# dac_audio_out.net
KiCad netlist of a schematic drawn in Altium Designer
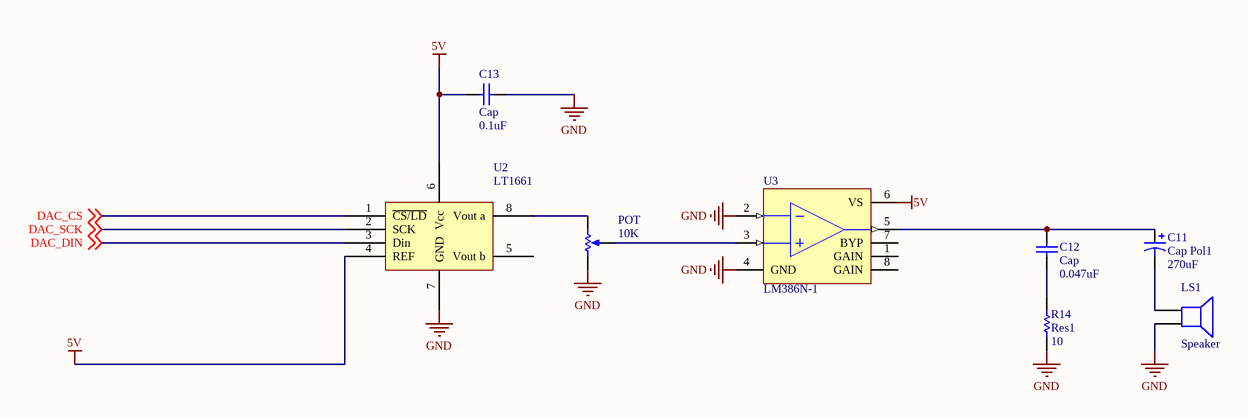
[diagram p0: dac_audio_out.SchDoc]

(export (version "E")
  (design (tool "Eeschema 10.0.6"))
  (components
    (comp (ref "C11")
      (value "Cap Pol1")
      (footprint "6-0805_M")
      (description "Polarized Capacitor (Radial)")
      (fields (field (name "ALTIUM_VALUE") "270uF") (field (name "PUBLISHER") "Altium Limited"))
      (libsource (lib "Miscellaneous Devices") (part "Cap Pol1"))
    )
    (comp (ref "C12")
      (value "Cap")
      (footprint "6-0805_M")
      (description "Capacitor")
      (fields (field (name "ALTIUM_VALUE") "0.047uF") (field (name "PUBLISHER") "Altium Limited"))
      (libsource (lib "Miscellaneous Devices") (part "Cap"))
    )
    (comp (ref "C13")
      (value "Cap")
      (footprint "6-0805_M")
      (description "Capacitor")
      (fields (field (name "ALTIUM_VALUE") "0.1uF") (field (name "PUBLISHER") "Altium Limited"))
      (libsource (lib "Miscellaneous Devices") (part "Cap"))
    )
    (comp (ref "LS1")
      (value "Speaker")
      (footprint "PIN2")
      (description "Loudspeaker")
      (fields (field (name "PUBLISHER") "Altium Limited"))
      (libsource (lib "Miscellaneous Devices") (part "Speaker"))
    )
    (comp (ref "POT")
      (value "10K")
      (footprint "VR5")
      (description "Potentiometer")
      (fields (field (name "Comment") "RPot_3") (field (name "PUBLISHER") "Altium Limited"))
      (libsource (lib "ECE LIB new") (part "RPot"))
    )
    (comp (ref "R14")
      (value "Res1")
      (footprint "6-0805_M")
      (description "Resistor")
      (fields (field (name "ALTIUM_VALUE") "10") (field (name "PUBLISHER") "Altium Limited"))
      (libsource (lib "Miscellaneous Devices") (part "Res1"))
    )
    (comp (ref "U2") (value "LT1661") (footprint "DIP-8") (libsource (lib "ECE LIB new") (part "LT1661")))
    (comp (ref "U3")
      (value "LM386N-1")
      (footprint "DIP-8")
      (description "Low-Voltage Audio Power Amplifier")
      (fields (field (name "PUBLISHER") "Altium Limited"))
      (libsource (lib "ECE LIB new") (part "LM386N-1"))
    )
  )
  (nets
    (net (code "1") (name "5V") (class "Default")
      (node (ref "C13") (pin "1") (pinfunction "1_1") (pintype "passive"))
      (node (ref "U2") (pin "4") (pinfunction "REF_4") (pintype "passive"))
      (node (ref "U2") (pin "6") (pinfunction "Vcc_6") (pintype "passive"))
      (node (ref "U3") (pin "6") (pinfunction "VS_6") (pintype "power_in"))
    )
    (net (code "2") (name "DAC_CS") (class "Default")
      (node (ref "U2") (pin "1") (pinfunction "~{CS/LD}_1") (pintype "passive"))
    )
    (net (code "3") (name "DAC_DIN") (class "Default")
      (node (ref "U2") (pin "3") (pinfunction "Din_3") (pintype "passive"))
    )
    (net (code "4") (name "DAC_SCK") (class "Default")
      (node (ref "U2") (pin "2") (pinfunction "SCK_2") (pintype "passive"))
    )
    (net (code "5") (name "GND") (class "Default")
      (node (ref "C13") (pin "2") (pinfunction "2_2") (pintype "passive"))
      (node (ref "LS1") (pin "2") (pinfunction "2_2") (pintype "passive"))
      (node (ref "POT") (pin "1") (pinfunction "TOP_1") (pintype "passive"))
      (node (ref "R14") (pin "1") (pinfunction "1_1") (pintype "passive"))
      (node (ref "U2") (pin "7") (pinfunction "GND_7") (pintype "passive"))
      (node (ref "U3") (pin "2") (pinfunction "IN-_2") (pintype "input"))
      (node (ref "U3") (pin "4") (pinfunction "GND_4") (pintype "power_in"))
    )
    (net (code "6") (name "Net-(C11-Pad2)") (class "Default")
      (node (ref "C11") (pin "2") (pinfunction "2_2") (pintype "passive"))
      (node (ref "LS1") (pin "1") (pinfunction "1_1") (pintype "passive"))
    )
    (net (code "7") (name "Net-(C12-Pad1)") (class "Default")
      (node (ref "C12") (pin "1") (pinfunction "1_1") (pintype "passive"))
      (node (ref "R14") (pin "2") (pinfunction "2_2") (pintype "passive"))
    )
    (net (code "8") (name "Net-(POT-BOT)") (class "Default")
      (node (ref "POT") (pin "3") (pinfunction "BOT_3") (pintype "passive"))
      (node (ref "U2") (pin "8") (pinfunction "Vout_a_8") (pintype "passive"))
    )
    (net (code "9") (name "Net-(POT-TAP)") (class "Default")
      (node (ref "POT") (pin "2") (pinfunction "TAP_2") (pintype "passive"))
      (node (ref "U3") (pin "3") (pinfunction "IN+_3") (pintype "input"))
    )
    (net (code "10") (name "Net-(U3-OUT)") (class "Default")
      (node (ref "C11") (pin "1") (pinfunction "1_1") (pintype "passive"))
      (node (ref "C12") (pin "2") (pinfunction "2_2") (pintype "passive"))
      (node (ref "U3") (pin "5") (pinfunction "OUT_5") (pintype "output"))
    )
    (net (code "11") (name "unconnected-(U2-Vout_b-Pad5)") (class "Default")
      (node (ref "U2") (pin "5") (pinfunction "Vout_b_5") (pintype "passive"))
    )
    (net (code "12") (name "unconnected-(U3-BYP-Pad7)") (class "Default")
      (node (ref "U3") (pin "7") (pinfunction "BYP_7") (pintype "passive"))
    )
    (net (code "13") (name "unconnected-(U3-GAIN-Pad1)") (class "Default")
      (node (ref "U3") (pin "1") (pinfunction "GAIN_1") (pintype "passive"))
    )
    (net (code "14") (name "unconnected-(U3-GAIN-Pad8)") (class "Default")
      (node (ref "U3") (pin "8") (pinfunction "GAIN_8") (pintype "passive"))
    )
  )
)
